# project_14.net
KiCad netlist of a schematic drawn in Altium Designer
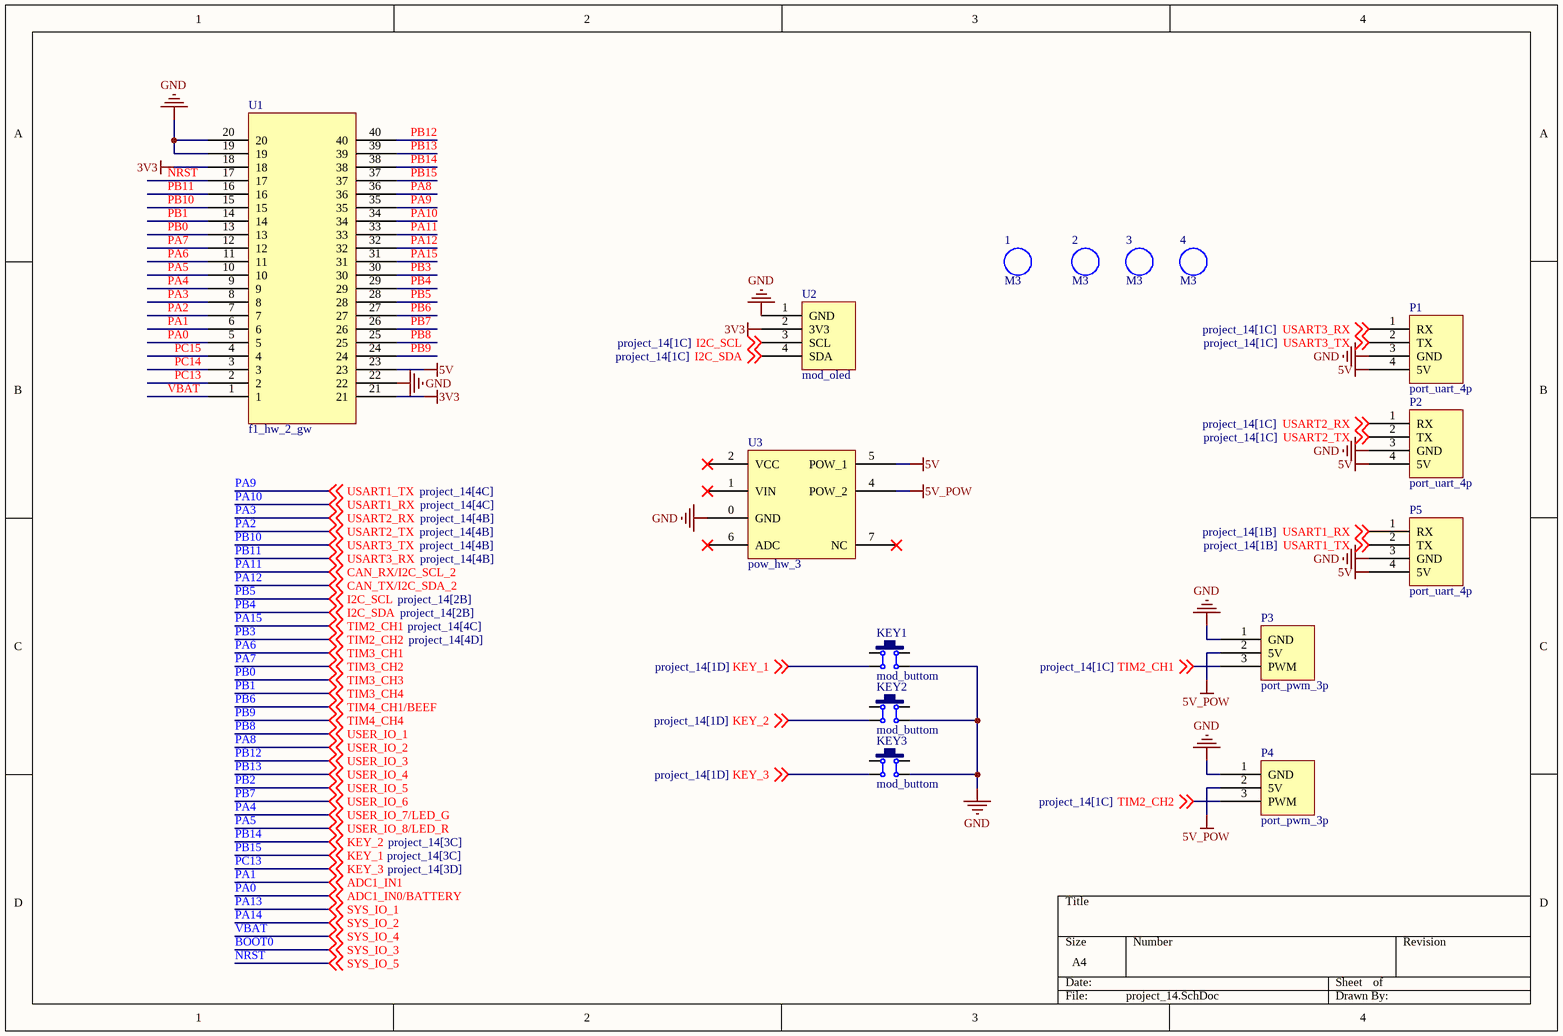
[diagram p0: project_14.SchDoc]

(export (version "E")
  (design (tool "Eeschema 10.0.6"))
  (components
    (comp (ref "1")
      (value "M3")
      (footprint "M3 125X200")
      (description "m3铜柱孔")
      (fields (field (name "版权归属") "源创客"))
      (libsource (lib "userLib") (part "prot_m3"))
    )
    (comp (ref "2")
      (value "M3")
      (footprint "M3 125X200")
      (description "m3铜柱孔")
      (fields (field (name "版权归属") "源创客"))
      (libsource (lib "userLib") (part "prot_m3"))
    )
    (comp (ref "3")
      (value "M3")
      (footprint "M3 125X200")
      (description "m3铜柱孔")
      (fields (field (name "版权归属") "源创客"))
      (libsource (lib "userLib") (part "prot_m3"))
    )
    (comp (ref "4")
      (value "M3")
      (footprint "M3 125X200")
      (description "m3铜柱孔")
      (fields (field (name "版权归属") "源创客"))
      (libsource (lib "userLib") (part "prot_m3"))
    )
    (comp (ref "KEY1")
      (value "mod_buttom")
      (footprint "MOD_BUTTOM")
      (description "6*6*4.3按键")
      (libsource (lib "userLib") (part "mod_buttom"))
    )
    (comp (ref "KEY2")
      (value "mod_buttom")
      (footprint "MOD_BUTTOM")
      (description "6*6*4.3按键")
      (libsource (lib "userLib") (part "mod_buttom"))
    )
    (comp (ref "KEY3")
      (value "mod_buttom")
      (footprint "MOD_BUTTOM")
      (description "6*6*4.3按键")
      (libsource (lib "userLib") (part "mod_buttom"))
    )
    (comp (ref "P1")
      (value "port_uart_4p")
      (footprint "XH2.54_4P")
      (description "串口接口/SPP蓝牙模块\r\nXH2.54弯排针4p/4p排母")
      (libsource (lib "userLib") (part "port_uart_4p"))
    )
    (comp (ref "P2")
      (value "port_uart_4p")
      (footprint "XH2.54_4P")
      (description "串口接口/SPP蓝牙模块\r\nXH2.54弯排针4p/4p排母")
      (libsource (lib "userLib") (part "port_uart_4p"))
    )
    (comp (ref "P3")
      (value "port_pwm_3p")
      (footprint "XH2.54_3P")
      (description "舵机接口\r\nXH2.54弯排针3p")
      (libsource (lib "userLib") (part "port_pwm_3p"))
    )
    (comp (ref "P4")
      (value "port_pwm_3p")
      (footprint "XH2.54_3P")
      (description "舵机接口\r\nXH2.54弯排针3p")
      (libsource (lib "userLib") (part "port_pwm_3p"))
    )
    (comp (ref "P5")
      (value "port_uart_4p")
      (footprint "XH2.54_4P")
      (description "串口接口/SPP蓝牙模块\r\nXH2.54弯排针4p/4p排母")
      (libsource (lib "userLib") (part "port_uart_4p"))
    )
    (comp (ref "U1")
      (value "f1_hw_2_gw")
      (footprint "F1_HW_2_GW")
      (libsource (lib "userLib") (part "f1_hw_2_gw"))
    )
    (comp (ref "U2")
      (value "mod_oled")
      (footprint "MOD_OLED")
      (description "oled模块\r\n4p排母")
      (libsource (lib "userLib") (part "mod_oled"))
    )
    (comp (ref "U3")
      (value "pow_hw_3")
      (footprint "POW_HW_3")
      (description "两路降压电源模块")
      (libsource (lib "userLib") (part "pow_hw_3"))
    )
  )
  (nets
    (net (code "1") (name "/PC14") (class "Default")
      (node (ref "U1") (pin "3") (pinfunction "3_3") (pintype "passive"))
    )
    (net (code "2") (name "/PC15") (class "Default")
      (node (ref "U1") (pin "4") (pinfunction "4_4") (pintype "passive"))
    )
    (net (code "3") (name "3V3") (class "Default")
      (node (ref "U1") (pin "18") (pinfunction "18_18") (pintype "passive"))
      (node (ref "U1") (pin "21") (pinfunction "21_21") (pintype "passive"))
      (node (ref "U2") (pin "2") (pinfunction "3V3_2") (pintype "passive"))
    )
    (net (code "4") (name "5V") (class "Default")
      (node (ref "P1") (pin "4") (pinfunction "5V_4") (pintype "passive"))
      (node (ref "P2") (pin "4") (pinfunction "5V_4") (pintype "passive"))
      (node (ref "P5") (pin "4") (pinfunction "5V_4") (pintype "passive"))
      (node (ref "U1") (pin "23") (pinfunction "23_23") (pintype "passive"))
      (node (ref "U3") (pin "5") (pinfunction "POW_1_5") (pintype "passive"))
    )
    (net (code "5") (name "5V_POW") (class "Default")
      (node (ref "P3") (pin "2") (pinfunction "5V_2") (pintype "passive"))
      (node (ref "P4") (pin "2") (pinfunction "5V_2") (pintype "passive"))
      (node (ref "U3") (pin "4") (pinfunction "POW_2_4") (pintype "passive"))
    )
    (net (code "6") (name "ADC1_IN0{slash}BATTERY") (class "Default")
      (node (ref "U1") (pin "5") (pinfunction "5_5") (pintype "passive"))
    )
    (net (code "7") (name "ADC1_IN1") (class "Default")
      (node (ref "U1") (pin "6") (pinfunction "6_6") (pintype "passive"))
    )
    (net (code "8") (name "CAN_RX{slash}I2C_SCL_2") (class "Default")
      (node (ref "U1") (pin "33") (pinfunction "33_33") (pintype "passive"))
    )
    (net (code "9") (name "CAN_TX{slash}I2C_SDA_2") (class "Default")
      (node (ref "U1") (pin "32") (pinfunction "32_32") (pintype "passive"))
    )
    (net (code "10") (name "GND") (class "Default")
      (node (ref "KEY1") (pin "3") (pinfunction "3_3") (pintype "passive"))
      (node (ref "KEY2") (pin "3") (pinfunction "3_3") (pintype "passive"))
      (node (ref "KEY3") (pin "3") (pinfunction "3_3") (pintype "passive"))
      (node (ref "P1") (pin "3") (pinfunction "GND_3") (pintype "passive"))
      (node (ref "P2") (pin "3") (pinfunction "GND_3") (pintype "passive"))
      (node (ref "P3") (pin "1") (pinfunction "GND_1") (pintype "passive"))
      (node (ref "P4") (pin "1") (pinfunction "GND_1") (pintype "passive"))
      (node (ref "P5") (pin "3") (pinfunction "GND_3") (pintype "passive"))
      (node (ref "U1") (pin "19") (pinfunction "19_19") (pintype "passive"))
      (node (ref "U1") (pin "20") (pinfunction "20_20") (pintype "passive"))
      (node (ref "U1") (pin "22") (pinfunction "22_22") (pintype "passive"))
      (node (ref "U2") (pin "1") (pinfunction "GND_1") (pintype "passive"))
      (node (ref "U3") (pin "0") (pinfunction "GND_0") (pintype "passive"))
    )
    (net (code "11") (name "I2C_SCL") (class "Default")
      (node (ref "U1") (pin "28") (pinfunction "28_28") (pintype "passive"))
      (node (ref "U2") (pin "3") (pinfunction "SCL_3") (pintype "passive"))
    )
    (net (code "12") (name "I2C_SDA") (class "Default")
      (node (ref "U1") (pin "29") (pinfunction "29_29") (pintype "passive"))
      (node (ref "U2") (pin "4") (pinfunction "SDA_4") (pintype "passive"))
    )
    (net (code "13") (name "KEY_1") (class "Default")
      (node (ref "KEY1") (pin "4") (pinfunction "4_4") (pintype "passive"))
      (node (ref "U1") (pin "37") (pinfunction "37_37") (pintype "passive"))
    )
    (net (code "14") (name "KEY_2") (class "Default")
      (node (ref "KEY2") (pin "4") (pinfunction "4_4") (pintype "passive"))
      (node (ref "U1") (pin "38") (pinfunction "38_38") (pintype "passive"))
    )
    (net (code "15") (name "KEY_3") (class "Default")
      (node (ref "KEY3") (pin "4") (pinfunction "4_4") (pintype "passive"))
      (node (ref "U1") (pin "2") (pinfunction "2_2") (pintype "passive"))
    )
    (net (code "19") (name "SYS_IO_4") (class "Default")
      (node (ref "U1") (pin "1") (pinfunction "1_1") (pintype "passive"))
    )
    (net (code "20") (name "SYS_IO_5") (class "Default")
      (node (ref "U1") (pin "17") (pinfunction "17_17") (pintype "passive"))
    )
    (net (code "21") (name "TIM2_CH1") (class "Default")
      (node (ref "P3") (pin "3") (pinfunction "PWM_3") (pintype "passive"))
      (node (ref "U1") (pin "31") (pinfunction "31_31") (pintype "passive"))
    )
    (net (code "22") (name "TIM2_CH2") (class "Default")
      (node (ref "P4") (pin "3") (pinfunction "PWM_3") (pintype "passive"))
      (node (ref "U1") (pin "30") (pinfunction "30_30") (pintype "passive"))
    )
    (net (code "23") (name "TIM3_CH1") (class "Default")
      (node (ref "U1") (pin "11") (pinfunction "11_11") (pintype "passive"))
    )
    (net (code "24") (name "TIM3_CH2") (class "Default")
      (node (ref "U1") (pin "12") (pinfunction "12_12") (pintype "passive"))
    )
    (net (code "25") (name "TIM3_CH3") (class "Default")
      (node (ref "U1") (pin "13") (pinfunction "13_13") (pintype "passive"))
    )
    (net (code "26") (name "TIM3_CH4") (class "Default")
      (node (ref "U1") (pin "14") (pinfunction "14_14") (pintype "passive"))
    )
    (net (code "27") (name "TIM4_CH1{slash}BEEF") (class "Default")
      (node (ref "U1") (pin "27") (pinfunction "27_27") (pintype "passive"))
    )
    (net (code "28") (name "TIM4_CH4") (class "Default")
      (node (ref "U1") (pin "24") (pinfunction "24_24") (pintype "passive"))
    )
    (net (code "29") (name "USART1_RX") (class "Default")
      (node (ref "P5") (pin "1") (pinfunction "RX_1") (pintype "passive"))
      (node (ref "U1") (pin "34") (pinfunction "34_34") (pintype "passive"))
    )
    (net (code "30") (name "USART1_TX") (class "Default")
      (node (ref "P5") (pin "2") (pinfunction "TX_2") (pintype "passive"))
      (node (ref "U1") (pin "35") (pinfunction "35_35") (pintype "passive"))
    )
    (net (code "31") (name "USART2_RX") (class "Default")
      (node (ref "P2") (pin "1") (pinfunction "RX_1") (pintype "passive"))
      (node (ref "U1") (pin "8") (pinfunction "8_8") (pintype "passive"))
    )
    (net (code "32") (name "USART2_TX") (class "Default")
      (node (ref "P2") (pin "2") (pinfunction "TX_2") (pintype "passive"))
      (node (ref "U1") (pin "7") (pinfunction "7_7") (pintype "passive"))
    )
    (net (code "33") (name "USART3_RX") (class "Default")
      (node (ref "P1") (pin "1") (pinfunction "RX_1") (pintype "passive"))
      (node (ref "U1") (pin "16") (pinfunction "16_16") (pintype "passive"))
    )
    (net (code "34") (name "USART3_TX") (class "Default")
      (node (ref "P1") (pin "2") (pinfunction "TX_2") (pintype "passive"))
      (node (ref "U1") (pin "15") (pinfunction "15_15") (pintype "passive"))
    )
    (net (code "35") (name "USER_IO_1") (class "Default")
      (node (ref "U1") (pin "25") (pinfunction "25_25") (pintype "passive"))
    )
    (net (code "36") (name "USER_IO_2") (class "Default")
      (node (ref "U1") (pin "36") (pinfunction "36_36") (pintype "passive"))
    )
    (net (code "37") (name "USER_IO_3") (class "Default")
      (node (ref "U1") (pin "40") (pinfunction "40_40") (pintype "passive"))
    )
    (net (code "38") (name "USER_IO_4") (class "Default")
      (node (ref "U1") (pin "39") (pinfunction "39_39") (pintype "passive"))
    )
    (net (code "40") (name "USER_IO_6") (class "Default")
      (node (ref "U1") (pin "26") (pinfunction "26_26") (pintype "passive"))
    )
    (net (code "41") (name "USER_IO_7{slash}LED_G") (class "Default")
      (node (ref "U1") (pin "9") (pinfunction "9_9") (pintype "passive"))
    )
    (net (code "42") (name "USER_IO_8{slash}LED_R") (class "Default")
      (node (ref "U1") (pin "10") (pinfunction "10_10") (pintype "passive"))
    )
    (net (code "43") (name "unconnected-(KEY1-Pad1)") (class "Default")
      (node (ref "KEY1") (pin "1") (pinfunction "1_1") (pintype "passive"))
    )
    (net (code "44") (name "unconnected-(KEY1-Pad2)") (class "Default")
      (node (ref "KEY1") (pin "2") (pinfunction "2_2") (pintype "passive"))
    )
    (net (code "45") (name "unconnected-(KEY2-Pad1)") (class "Default")
      (node (ref "KEY2") (pin "1") (pinfunction "1_1") (pintype "passive"))
    )
    (net (code "46") (name "unconnected-(KEY2-Pad2)") (class "Default")
      (node (ref "KEY2") (pin "2") (pinfunction "2_2") (pintype "passive"))
    )
    (net (code "47") (name "unconnected-(KEY3-Pad1)") (class "Default")
      (node (ref "KEY3") (pin "1") (pinfunction "1_1") (pintype "passive"))
    )
    (net (code "48") (name "unconnected-(KEY3-Pad2)") (class "Default")
      (node (ref "KEY3") (pin "2") (pinfunction "2_2") (pintype "passive"))
    )
    (net (code "49") (name "unconnected-(U3-ADC-Pad6)") (class "Default")
      (node (ref "U3") (pin "6") (pinfunction "ADC_6") (pintype "passive+no_connect"))
    )
    (net (code "50") (name "unconnected-(U3-NC-Pad7)") (class "Default")
      (node (ref "U3") (pin "7") (pinfunction "NC_7") (pintype "passive+no_connect"))
    )
    (net (code "51") (name "unconnected-(U3-VCC-Pad2)") (class "Default")
      (node (ref "U3") (pin "2") (pinfunction "VCC_2") (pintype "passive+no_connect"))
    )
    (net (code "52") (name "unconnected-(U3-VIN-Pad1)") (class "Default")
      (node (ref "U3") (pin "1") (pinfunction "VIN_1") (pintype "passive+no_connect"))
    )
  )
)
